# HF_AMP_DRIVER.net
KiCad netlist of a schematic drawn in Altium Designer
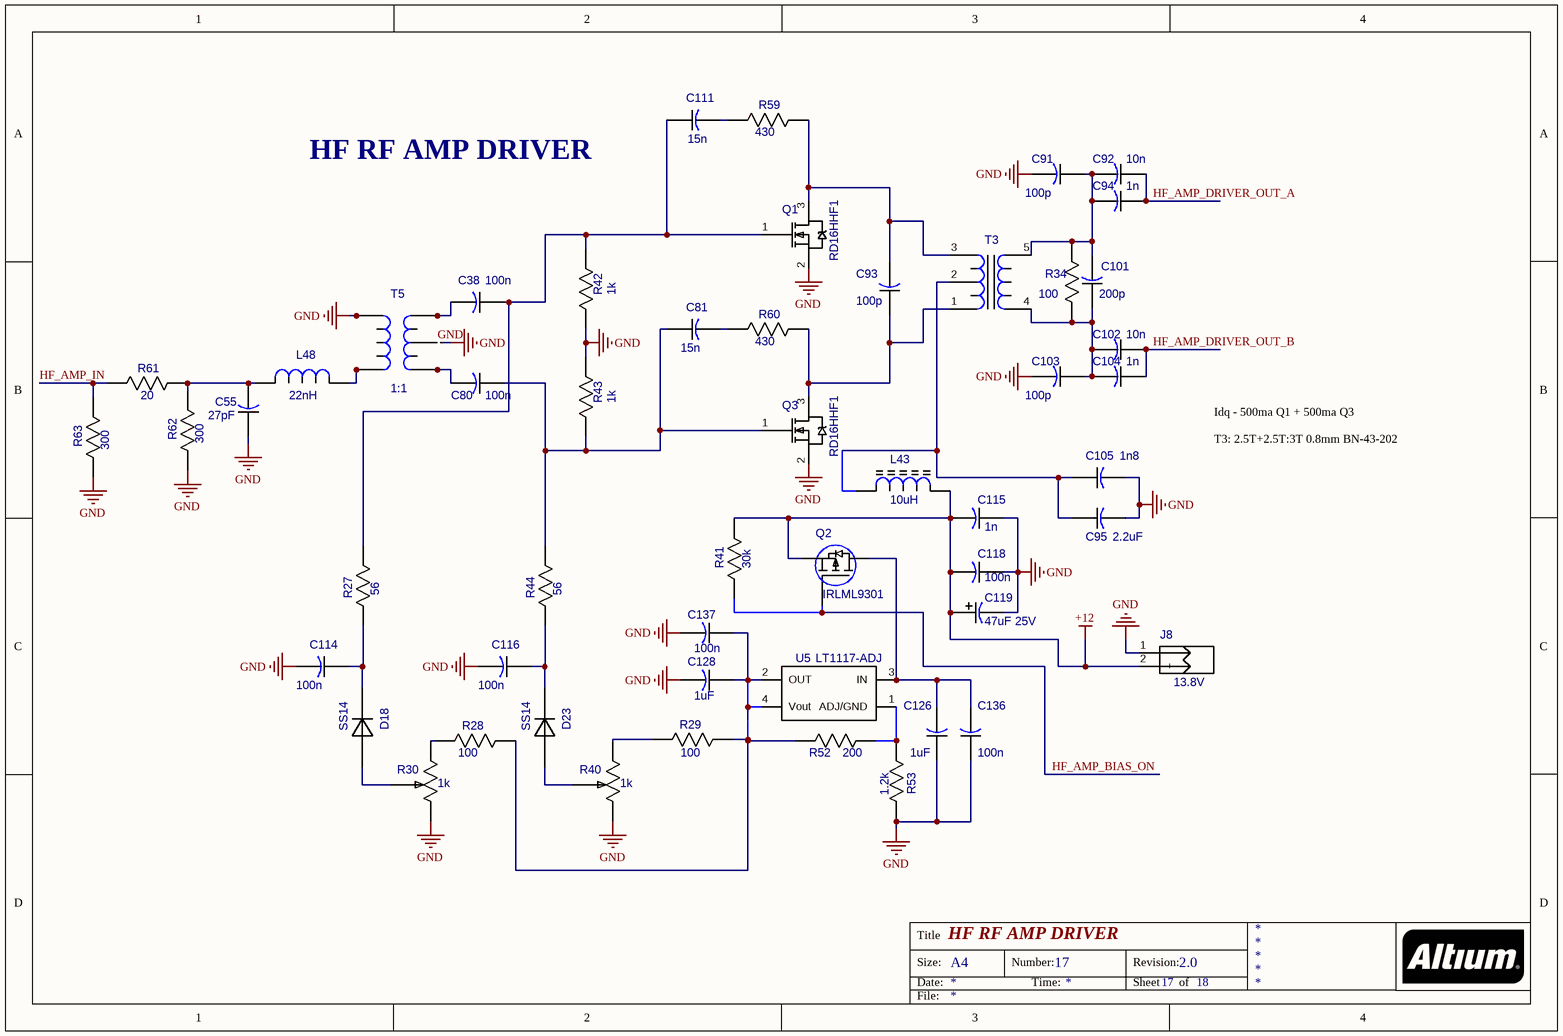
[diagram p0: HF_AMP_DRIVER.SchDoc]

(export (version "E")
  (design (tool "Eeschema 10.0.6"))
  (components
    (comp (ref "C38")
      (value "100n")
      (footprint "CAP_0805")
      (description "CAP_0805")
      (libsource (lib "*") (part "CAP_0805"))
    )
    (comp (ref "C55")
      (value "27pF")
      (footprint "CAP_0805")
      (description "CAP_0805")
      (libsource (lib "*") (part "CAP_0805"))
    )
    (comp (ref "C80")
      (value "100n")
      (footprint "CAP_0805")
      (description "CAP_0805")
      (libsource (lib "*") (part "CAP_0805"))
    )
    (comp (ref "C81")
      (value "15n")
      (footprint "CAP_1206")
      (description "CAP_1206")
      (libsource (lib "*") (part "CAP_1206"))
    )
    (comp (ref "C91")
      (value "100p")
      (footprint "CAP_1206")
      (description "CAP_1206")
      (libsource (lib "*") (part "CAP_1206"))
    )
    (comp (ref "C92")
      (value "10n")
      (footprint "CAP_1206")
      (description "CAP_1206")
      (libsource (lib "*") (part "CAP_1206"))
    )
    (comp (ref "C93")
      (value "100p")
      (footprint "CAP_1206")
      (description "CAP_1206")
      (libsource (lib "*") (part "CAP_1206"))
    )
    (comp (ref "C94")
      (value "1n")
      (footprint "CAP_1206")
      (description "CAP_1206")
      (libsource (lib "*") (part "CAP_1206"))
    )
    (comp (ref "C95")
      (value "2.2uF")
      (footprint "CAP_1206")
      (description "CAP_1206")
      (libsource (lib "*") (part "CAP_1206"))
    )
    (comp (ref "C101")
      (value "200p")
      (footprint "CAP_1206")
      (description "CAP_1206")
      (libsource (lib "*") (part "CAP_1206"))
    )
    (comp (ref "C102")
      (value "10n")
      (footprint "CAP_1206")
      (description "CAP_1206")
      (libsource (lib "*") (part "CAP_1206"))
    )
    (comp (ref "C103")
      (value "100p")
      (footprint "CAP_1206")
      (description "CAP_1206")
      (libsource (lib "*") (part "CAP_1206"))
    )
    (comp (ref "C104")
      (value "1n")
      (footprint "CAP_1206")
      (description "CAP_1206")
      (libsource (lib "*") (part "CAP_1206"))
    )
    (comp (ref "C105")
      (value "1n8")
      (footprint "CAP_1206")
      (description "CAP_1206")
      (libsource (lib "*") (part "CAP_1206"))
    )
    (comp (ref "C111")
      (value "15n")
      (footprint "CAP_1206")
      (description "CAP_1206")
      (libsource (lib "*") (part "CAP_1206"))
    )
    (comp (ref "C114")
      (value "100n")
      (footprint "CAP_0805")
      (description "CAP_0805")
      (libsource (lib "*") (part "CAP_0805"))
    )
    (comp (ref "C115")
      (value "1n")
      (footprint "CAP_0805")
      (description "CAP_0805")
      (libsource (lib "*") (part "CAP_0805"))
    )
    (comp (ref "C116")
      (value "100n")
      (footprint "CAP_0805")
      (description "CAP_0805")
      (libsource (lib "*") (part "CAP_0805"))
    )
    (comp (ref "C118")
      (value "100n")
      (footprint "CAP_0805")
      (description "CAP_0805")
      (libsource (lib "*") (part "CAP_0805"))
    )
    (comp (ref "C119")
      (value "47uF 25V")
      (footprint "CAPAE_6.6x6.6h5.4")
      (description "CAPAE_6.6x6.6h5.4")
      (libsource (lib "*") (part "CAPAE_6.6x6.6h5.4"))
    )
    (comp (ref "C126")
      (value "1uF")
      (footprint "CAP_0805")
      (description "CAP_0805")
      (libsource (lib "*") (part "CAP_0805"))
    )
    (comp (ref "C128")
      (value "1uF")
      (footprint "CAP_0805")
      (description "CAP_0805")
      (libsource (lib "*") (part "CAP_0805"))
    )
    (comp (ref "C136")
      (value "100n")
      (footprint "CAP_0805")
      (description "CAP_0805")
      (libsource (lib "*") (part "CAP_0805"))
    )
    (comp (ref "C137")
      (value "100n")
      (footprint "CAP_0805")
      (description "CAP_0805")
      (libsource (lib "*") (part "CAP_0805"))
    )
    (comp (ref "D18") (value "SS14") (footprint "SS14") (libsource (lib "*") (part "SS14")))
    (comp (ref "D23") (value "SS14") (footprint "SS14") (libsource (lib "*") (part "SS14")))
    (comp (ref "J8")
      (value "13.8V")
      (footprint "1986717-2")
      (description "JX2")
      (libsource (lib "*") (part "1986717-2"))
    )
    (comp (ref "L43")
      (value "10uH")
      (footprint "IND_FERRITE_CORE")
      (description "Inductor")
      (libsource (lib "*") (part "IND_FERRITE_CORE"))
    )
    (comp (ref "L48")
      (value "22nH")
      (footprint "IND_0805")
      (description "IND_0805")
      (libsource (lib "*") (part "IND_0805"))
    )
    (comp (ref "Q1")
      (value "RD16HHF1")
      (footprint "RD16_V2")
      (libsource (lib "RF-UNIT-BIG") (part "RD16HHF1"))
    )
    (comp (ref "Q2")
      (value "IRLML9301")
      (footprint "SOT23")
      (description "MOSFET")
      (libsource (lib "*") (part "MOSFET_ENH_PD"))
    )
    (comp (ref "Q3")
      (value "RD16HHF1")
      (footprint "RD16_V2")
      (libsource (lib "RF-UNIT-BIG") (part "RD16HHF1"))
    )
    (comp (ref "R27")
      (value "56")
      (footprint "RES_0805")
      (description "RES_0805")
      (libsource (lib "*") (part "RES_0805"))
    )
    (comp (ref "R28")
      (value "100")
      (footprint "RES_0805")
      (description "RES_0805")
      (libsource (lib "*") (part "RES_0805"))
    )
    (comp (ref "R29")
      (value "100")
      (footprint "RES_0805")
      (description "RES_0805")
      (libsource (lib "*") (part "RES_0805"))
    )
    (comp (ref "R30")
      (value "1k")
      (footprint "306J")
      (description "306J")
      (fields (field (name "Comment") "ADJ-1k"))
      (libsource (lib "*") (part "306J"))
    )
    (comp (ref "R34")
      (value "100")
      (footprint "RES_1206")
      (description "RES_1206")
      (libsource (lib "*") (part "RES_1206"))
    )
    (comp (ref "R40")
      (value "1k")
      (footprint "306J")
      (description "306J")
      (fields (field (name "Comment") "ADJ-1k"))
      (libsource (lib "*") (part "306J"))
    )
    (comp (ref "R41")
      (value "30k")
      (footprint "RES_0805")
      (description "RES_0805")
      (libsource (lib "*") (part "RES_0805"))
    )
    (comp (ref "R42")
      (value "1k")
      (footprint "RES_0805")
      (description "RES_0805")
      (libsource (lib "*") (part "RES_0805"))
    )
    (comp (ref "R43")
      (value "1k")
      (footprint "RES_0805")
      (description "RES_0805")
      (libsource (lib "*") (part "RES_0805"))
    )
    (comp (ref "R44")
      (value "56")
      (footprint "RES_0805")
      (description "RES_0805")
      (libsource (lib "*") (part "RES_0805"))
    )
    (comp (ref "R52")
      (value "200")
      (footprint "RES_0805")
      (description "RES_0805")
      (libsource (lib "*") (part "RES_0805"))
    )
    (comp (ref "R53")
      (value "1.2k")
      (footprint "RES_0805")
      (description "RES_0805")
      (libsource (lib "*") (part "RES_0805"))
    )
    (comp (ref "R59")
      (value "430")
      (footprint "RES_1206")
      (description "RES_1206")
      (libsource (lib "*") (part "RES_1206"))
    )
    (comp (ref "R60")
      (value "430")
      (footprint "RES_1206")
      (description "RES_1206")
      (libsource (lib "*") (part "RES_1206"))
    )
    (comp (ref "R61")
      (value "20")
      (footprint "RES_1206")
      (description "RES_1206")
      (libsource (lib "*") (part "RES_1206"))
    )
    (comp (ref "R62")
      (value "300")
      (footprint "RES_1206")
      (description "RES_1206")
      (libsource (lib "*") (part "RES_1206"))
    )
    (comp (ref "R63")
      (value "300")
      (footprint "RES_1206")
      (description "RES_1206")
      (libsource (lib "*") (part "RES_1206"))
    )
    (comp (ref "T3")
      (value "TRANSF_HF3")
      (footprint "TRANSF_HF3")
      (libsource (lib "RF-UNIT-BIG") (part "TRANSF_RF3"))
    )
    (comp (ref "T5")
      (value "1:1")
      (footprint "TRANSF_ACORE2")
      (libsource (lib "RF-UNIT_1") (part "TRANSF_ACORE2"))
    )
    (comp (ref "U5")
      (value "LT1117-ADJ")
      (footprint "LT1117IST-ADJ")
      (description "LT1117IST-ADJ")
      (libsource (lib "*") (part "LT1117IST-ADJ"))
    )
  )
  (nets
    (net (code "1") (name "+12") (class "Default")
      (node (ref "C115") (pin "2") (pinfunction "2_2") (pintype "passive"))
      (node (ref "C118") (pin "2") (pinfunction "2_2") (pintype "passive"))
      (node (ref "C119") (pin "1") (pinfunction "PLUS_1") (pintype "passive"))
      (node (ref "J8") (pin "2") (pinfunction "+_2") (pintype "passive"))
      (node (ref "L43") (pin "2") (pinfunction "B_2") (pintype "passive"))
      (node (ref "Q2") (pin "2") (pinfunction "S_2") (pintype "passive"))
      (node (ref "R41") (pin "2") (pinfunction "2_2") (pintype "passive"))
    )
    (net (code "2") (name "/HF_AMP_BIAS_ON") (class "Default")
      (node (ref "Q2") (pin "1") (pinfunction "G_1") (pintype "passive"))
      (node (ref "R41") (pin "1") (pinfunction "1_1") (pintype "passive"))
    )
    (net (code "3") (name "/HF_AMP_DRIVER_OUT_A") (class "Default")
      (node (ref "C92") (pin "1") (pinfunction "1_1") (pintype "passive"))
      (node (ref "C94") (pin "1") (pinfunction "1_1") (pintype "passive"))
    )
    (net (code "4") (name "/HF_AMP_DRIVER_OUT_B") (class "Default")
      (node (ref "C102") (pin "1") (pinfunction "1_1") (pintype "passive"))
      (node (ref "C104") (pin "1") (pinfunction "1_1") (pintype "passive"))
    )
    (net (code "5") (name "/HF_AMP_IN") (class "Default")
      (node (ref "R61") (pin "1") (pinfunction "1_1") (pintype "passive"))
      (node (ref "R63") (pin "2") (pinfunction "2_2") (pintype "passive"))
    )
    (net (code "6") (name "GND") (class "Default")
      (node (ref "C103") (pin "2") (pinfunction "2_2") (pintype "passive"))
      (node (ref "C105") (pin "2") (pinfunction "2_2") (pintype "passive"))
      (node (ref "C114") (pin "2") (pinfunction "2_2") (pintype "passive"))
      (node (ref "C115") (pin "1") (pinfunction "1_1") (pintype "passive"))
      (node (ref "C116") (pin "2") (pinfunction "2_2") (pintype "passive"))
      (node (ref "C118") (pin "1") (pinfunction "1_1") (pintype "passive"))
      (node (ref "C119") (pin "2") (pinfunction "MINUS_2") (pintype "passive"))
      (node (ref "C126") (pin "1") (pinfunction "1_1") (pintype "passive"))
      (node (ref "C128") (pin "2") (pinfunction "2_2") (pintype "passive"))
      (node (ref "C136") (pin "1") (pinfunction "1_1") (pintype "passive"))
      (node (ref "C137") (pin "2") (pinfunction "2_2") (pintype "passive"))
      (node (ref "C55") (pin "1") (pinfunction "1_1") (pintype "passive"))
      (node (ref "C91") (pin "2") (pinfunction "2_2") (pintype "passive"))
      (node (ref "C95") (pin "2") (pinfunction "2_2") (pintype "passive"))
      (node (ref "J8") (pin "1") (pinfunction "-_1") (pintype "passive"))
      (node (ref "Q1") (pin "2") (pinfunction "S_2") (pintype "passive"))
      (node (ref "Q3") (pin "2") (pinfunction "S_2") (pintype "passive"))
      (node (ref "R30") (pin "1") (pinfunction "CCW_1") (pintype "passive"))
      (node (ref "R40") (pin "1") (pinfunction "CCW_1") (pintype "passive"))
      (node (ref "R42") (pin "1") (pinfunction "1_1") (pintype "passive"))
      (node (ref "R43") (pin "2") (pinfunction "2_2") (pintype "passive"))
      (node (ref "R53") (pin "2") (pinfunction "2_2") (pintype "passive"))
      (node (ref "R62") (pin "1") (pinfunction "1_1") (pintype "passive"))
      (node (ref "R63") (pin "1") (pinfunction "1_1") (pintype "passive"))
      (node (ref "T5") (pin "11") (pinfunction "0_11") (pintype "passive"))
      (node (ref "T5") (pin "2") (pinfunction "S2_2") (pintype "passive"))
      (node (ref "T5") (pin "4") (pinfunction "P2_4") (pintype "passive"))
      (node (ref "T5") (pin "8") (pinfunction "S2_8") (pintype "passive"))
    )
    (net (code "7") (name "Net-(C55-Pad2)") (class "Default")
      (node (ref "C55") (pin "2") (pinfunction "2_2") (pintype "passive"))
      (node (ref "L48") (pin "1") (pinfunction "1_1") (pintype "passive"))
      (node (ref "R61") (pin "2") (pinfunction "2_2") (pintype "passive"))
      (node (ref "R62") (pin "2") (pinfunction "2_2") (pintype "passive"))
    )
    (net (code "8") (name "Net-(C81-Pad2)") (class "Default")
      (node (ref "C81") (pin "2") (pinfunction "2_2") (pintype "passive"))
      (node (ref "R60") (pin "1") (pinfunction "1_1") (pintype "passive"))
    )
    (net (code "9") (name "Net-(C111-Pad2)") (class "Default")
      (node (ref "C111") (pin "2") (pinfunction "2_2") (pintype "passive"))
      (node (ref "R59") (pin "1") (pinfunction "1_1") (pintype "passive"))
    )
    (net (code "10") (name "Net-(D18-A)") (class "Default")
      (node (ref "D18") (pin "2") (pinfunction "A_2") (pintype "passive"))
      (node (ref "R30") (pin "2") (pinfunction "W_2") (pintype "passive"))
    )
    (net (code "11") (name "Net-(D18-K)") (class "Default")
      (node (ref "C114") (pin "1") (pinfunction "1_1") (pintype "passive"))
      (node (ref "D18") (pin "1") (pinfunction "K_1") (pintype "passive"))
      (node (ref "R27") (pin "1") (pinfunction "1_1") (pintype "passive"))
    )
    (net (code "12") (name "Net-(D23-A)") (class "Default")
      (node (ref "D23") (pin "2") (pinfunction "A_2") (pintype "passive"))
      (node (ref "R40") (pin "2") (pinfunction "W_2") (pintype "passive"))
    )
    (net (code "13") (name "Net-(D23-K)") (class "Default")
      (node (ref "C116") (pin "1") (pinfunction "1_1") (pintype "passive"))
      (node (ref "D23") (pin "1") (pinfunction "K_1") (pintype "passive"))
      (node (ref "R44") (pin "1") (pinfunction "1_1") (pintype "passive"))
    )
    (net (code "14") (name "Net-(L43-A)") (class "Default")
      (node (ref "C105") (pin "1") (pinfunction "1_1") (pintype "passive"))
      (node (ref "C95") (pin "1") (pinfunction "1_1") (pintype "passive"))
      (node (ref "L43") (pin "1") (pinfunction "A_1") (pintype "passive"))
      (node (ref "T3") (pin "2") (pinfunction "S3_2") (pintype "passive"))
    )
    (net (code "15") (name "Net-(Q1-D)") (class "Default")
      (node (ref "C93") (pin "2") (pinfunction "2_2") (pintype "passive"))
      (node (ref "Q1") (pin "3") (pinfunction "D_3") (pintype "passive"))
      (node (ref "R59") (pin "2") (pinfunction "2_2") (pintype "passive"))
      (node (ref "T3") (pin "3") (pinfunction "S1_3") (pintype "passive"))
    )
    (net (code "16") (name "Net-(Q1-G)") (class "Default")
      (node (ref "C111") (pin "1") (pinfunction "1_1") (pintype "passive"))
      (node (ref "C38") (pin "1") (pinfunction "1_1") (pintype "passive"))
      (node (ref "Q1") (pin "1") (pinfunction "G_1") (pintype "passive"))
      (node (ref "R27") (pin "2") (pinfunction "2_2") (pintype "passive"))
      (node (ref "R42") (pin "2") (pinfunction "2_2") (pintype "passive"))
    )
    (net (code "17") (name "Net-(Q2-D)") (class "Default")
      (node (ref "C126") (pin "2") (pinfunction "2_2") (pintype "passive"))
      (node (ref "C136") (pin "2") (pinfunction "2_2") (pintype "passive"))
      (node (ref "Q2") (pin "3") (pinfunction "D_3") (pintype "passive"))
      (node (ref "U5") (pin "3") (pinfunction "IN_3") (pintype "passive"))
    )
    (net (code "18") (name "Net-(Q3-D)") (class "Default")
      (node (ref "C93") (pin "1") (pinfunction "1_1") (pintype "passive"))
      (node (ref "Q3") (pin "3") (pinfunction "D_3") (pintype "passive"))
      (node (ref "R60") (pin "2") (pinfunction "2_2") (pintype "passive"))
      (node (ref "T3") (pin "1") (pinfunction "S2_1") (pintype "passive"))
    )
    (net (code "19") (name "Net-(Q3-G)") (class "Default")
      (node (ref "C80") (pin "1") (pinfunction "1_1") (pintype "passive"))
      (node (ref "C81") (pin "1") (pinfunction "1_1") (pintype "passive"))
      (node (ref "Q3") (pin "1") (pinfunction "G_1") (pintype "passive"))
      (node (ref "R43") (pin "1") (pinfunction "1_1") (pintype "passive"))
      (node (ref "R44") (pin "2") (pinfunction "2_2") (pintype "passive"))
    )
    (net (code "20") (name "Net-(R30-CW)") (class "Default")
      (node (ref "R28") (pin "1") (pinfunction "1_1") (pintype "passive"))
      (node (ref "R30") (pin "3") (pinfunction "CW_3") (pintype "passive"))
    )
    (net (code "21") (name "Net-(R40-CW)") (class "Default")
      (node (ref "R29") (pin "1") (pinfunction "1_1") (pintype "passive"))
      (node (ref "R40") (pin "3") (pinfunction "CW_3") (pintype "passive"))
    )
    (net (code "22") (name "Net-(T3-P1)") (class "Default")
      (node (ref "C101") (pin "2") (pinfunction "2_2") (pintype "passive"))
      (node (ref "C91") (pin "1") (pinfunction "1_1") (pintype "passive"))
      (node (ref "C92") (pin "2") (pinfunction "2_2") (pintype "passive"))
      (node (ref "C94") (pin "2") (pinfunction "2_2") (pintype "passive"))
      (node (ref "R34") (pin "2") (pinfunction "2_2") (pintype "passive"))
      (node (ref "T3") (pin "5") (pinfunction "P1_5") (pintype "passive"))
    )
    (net (code "23") (name "Net-(T3-P2)") (class "Default")
      (node (ref "C101") (pin "1") (pinfunction "1_1") (pintype "passive"))
      (node (ref "C102") (pin "2") (pinfunction "2_2") (pintype "passive"))
      (node (ref "C103") (pin "1") (pinfunction "1_1") (pintype "passive"))
      (node (ref "C104") (pin "2") (pinfunction "2_2") (pintype "passive"))
      (node (ref "R34") (pin "1") (pinfunction "1_1") (pintype "passive"))
      (node (ref "T3") (pin "4") (pinfunction "P2_4") (pintype "passive"))
    )
    (net (code "24") (name "Net-(T5-P1)") (class "Default")
      (node (ref "L48") (pin "2") (pinfunction "2_2") (pintype "passive"))
      (node (ref "T5") (pin "10") (pinfunction "0_10") (pintype "passive"))
      (node (ref "T5") (pin "6") (pinfunction "P1_6") (pintype "passive"))
    )
    (net (code "25") (name "Net-(T5-S1)") (class "Default")
      (node (ref "C80") (pin "2") (pinfunction "2_2") (pintype "passive"))
      (node (ref "T5") (pin "1") (pinfunction "S1_1") (pintype "passive"))
      (node (ref "T5") (pin "7") (pinfunction "0_7") (pintype "passive"))
    )
    (net (code "26") (name "Net-(T5-S3)") (class "Default")
      (node (ref "C38") (pin "2") (pinfunction "2_2") (pintype "passive"))
      (node (ref "T5") (pin "3") (pinfunction "S3_3") (pintype "passive"))
      (node (ref "T5") (pin "9") (pinfunction "0_9") (pintype "passive"))
    )
    (net (code "27") (name "Net-(U5-ADJ{slash}GND)") (class "Default")
      (node (ref "R52") (pin "2") (pinfunction "2_2") (pintype "passive"))
      (node (ref "R53") (pin "1") (pinfunction "1_1") (pintype "passive"))
      (node (ref "U5") (pin "1") (pinfunction "ADJ/GND_1") (pintype "passive"))
    )
    (net (code "28") (name "Net-(U5-OUT)") (class "Default")
      (node (ref "C128") (pin "1") (pinfunction "1_1") (pintype "passive"))
      (node (ref "C137") (pin "1") (pinfunction "1_1") (pintype "passive"))
      (node (ref "R28") (pin "2") (pinfunction "2_2") (pintype "passive"))
      (node (ref "R29") (pin "2") (pinfunction "2_2") (pintype "passive"))
      (node (ref "R52") (pin "1") (pinfunction "1_1") (pintype "passive"))
      (node (ref "U5") (pin "2") (pinfunction "OUT_2") (pintype "passive"))
      (node (ref "U5") (pin "4") (pinfunction "Vout_4") (pintype "passive"))
    )
  )
)
